# universal_front_plate_final.net
KiCad netlist of a schematic drawn in EAGLE
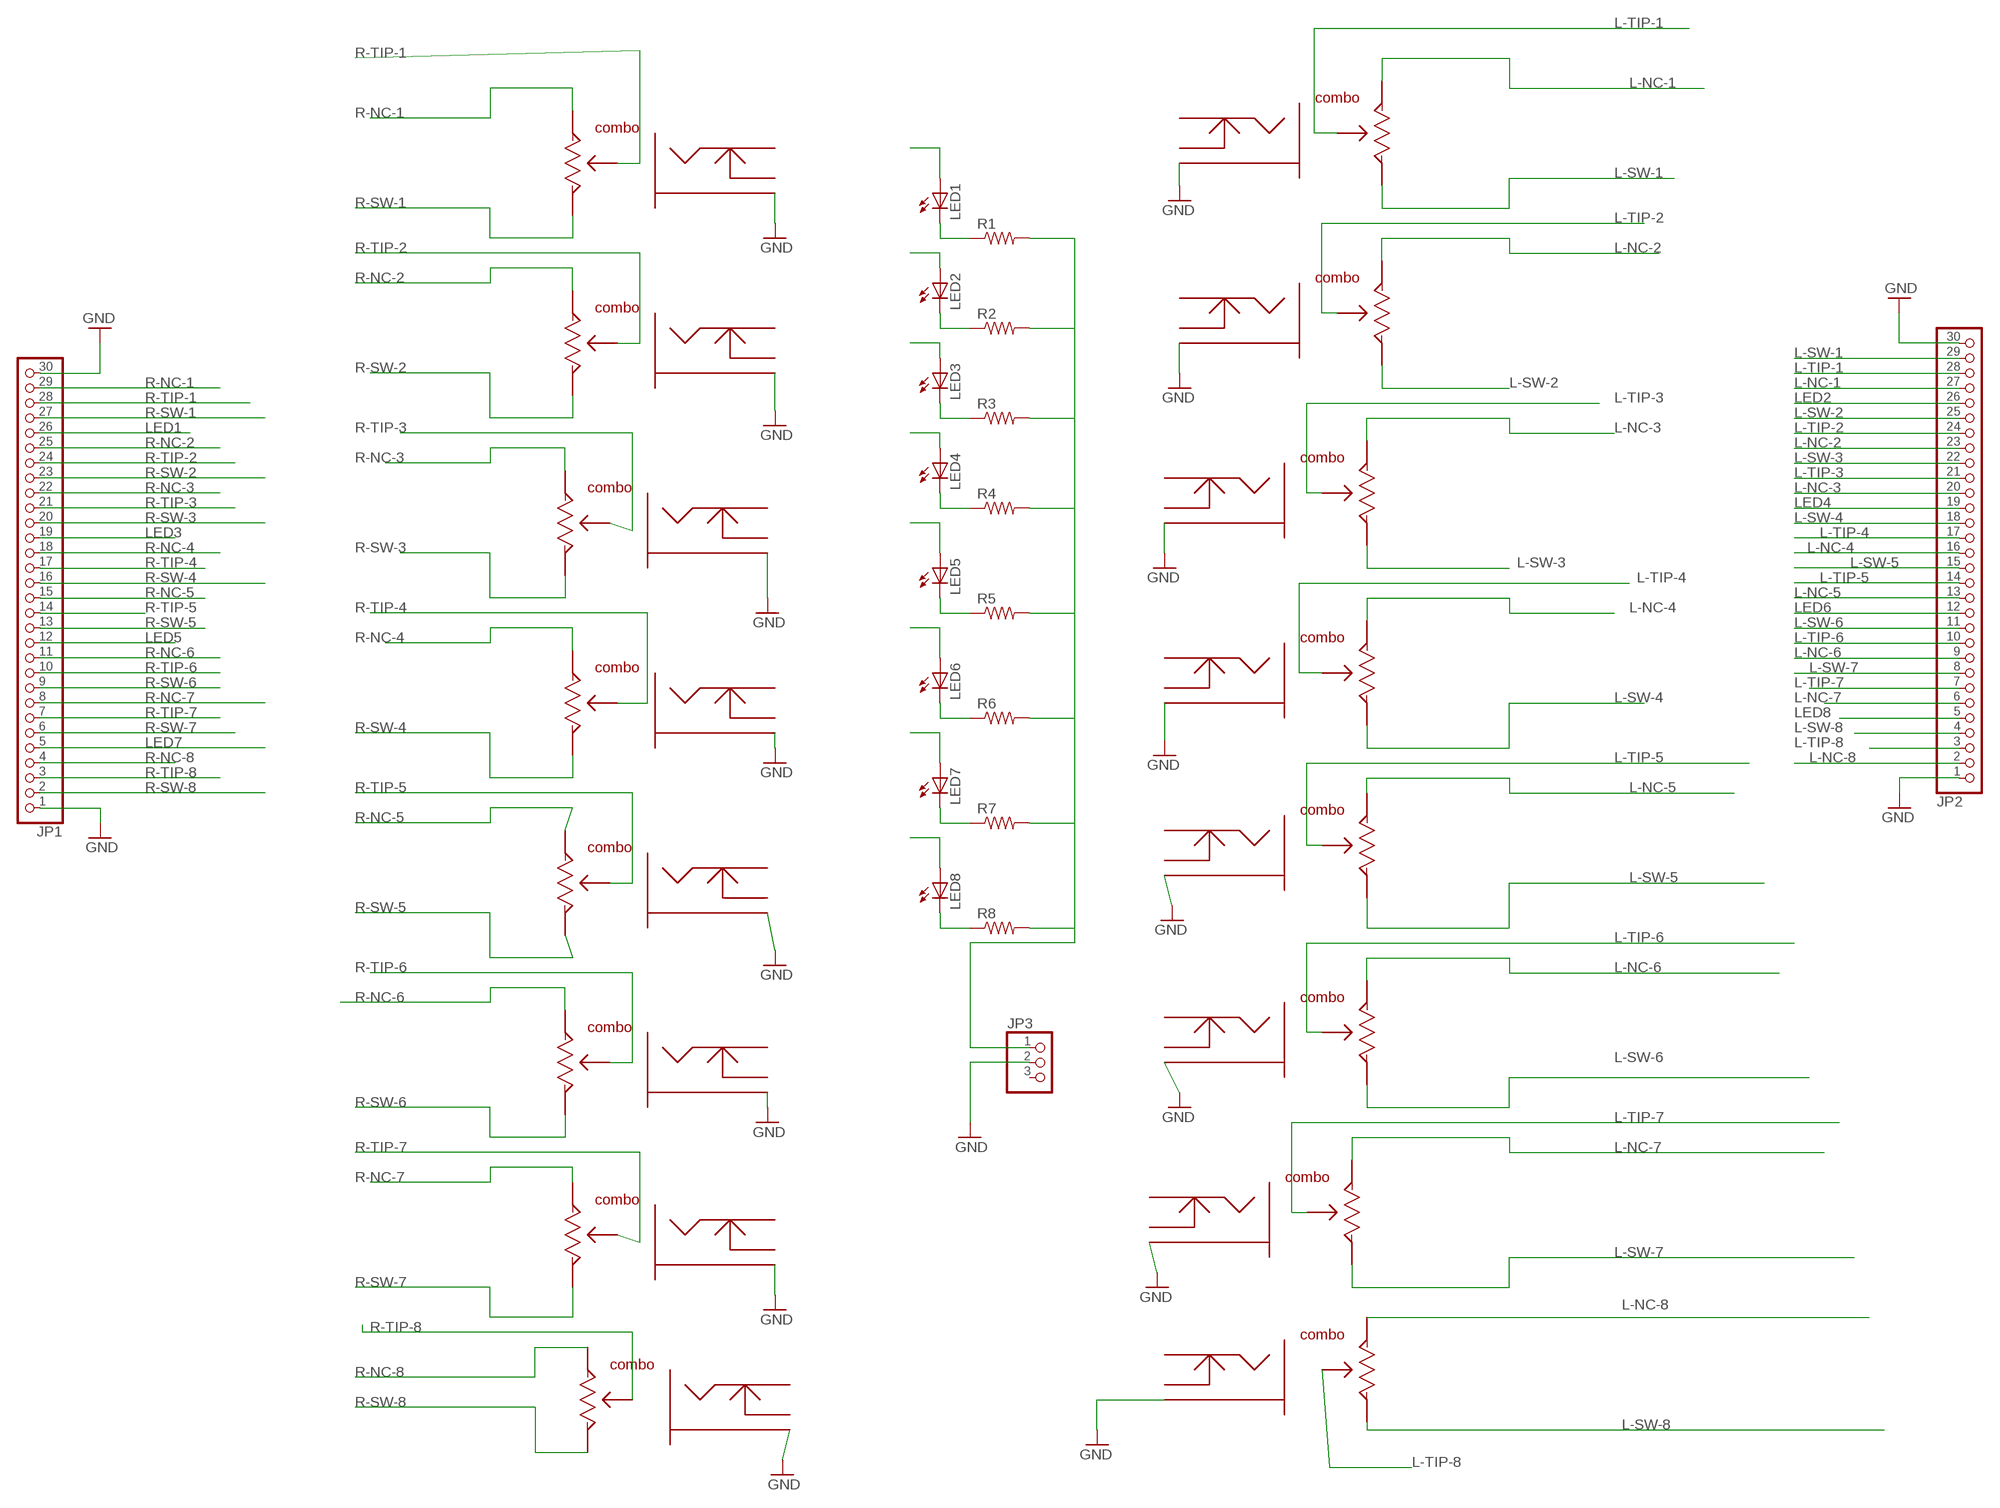
[diagram p0: schematic, sheet 1]

(export (version "E")
  (design (tool "Eeschema 10.0.6"))
  (components
    (comp (ref "JP1")
      (value "PINHD-1X30")
      (footprint "eagle-import:1X30")
      (libsource (lib "eagle-import") (part "PINHD-1X30"))
    )
    (comp (ref "JP2")
      (value "PINHD-1X30")
      (footprint "eagle-import:1X30")
      (libsource (lib "eagle-import") (part "PINHD-1X30"))
    )
    (comp (ref "JP3")
      (value "PINHD-1X3")
      (footprint "eagle-import:1X03")
      (libsource (lib "eagle-import") (part "PINHD-1X3"))
    )
    (comp (ref "LED1")
      (value "LED3MM")
      (footprint "eagle-import:LED3MM")
      (libsource (lib "eagle-import") (part "LED3MM"))
    )
    (comp (ref "LED2")
      (value "LED3MM")
      (footprint "eagle-import:LED3MM")
      (libsource (lib "eagle-import") (part "LED3MM"))
    )
    (comp (ref "LED3")
      (value "LED3MM")
      (footprint "eagle-import:LED3MM")
      (libsource (lib "eagle-import") (part "LED3MM"))
    )
    (comp (ref "LED4")
      (value "LED3MM")
      (footprint "eagle-import:LED3MM")
      (libsource (lib "eagle-import") (part "LED3MM"))
    )
    (comp (ref "LED5")
      (value "LED3MM")
      (footprint "eagle-import:LED3MM")
      (libsource (lib "eagle-import") (part "LED3MM"))
    )
    (comp (ref "LED6")
      (value "LED3MM")
      (footprint "eagle-import:LED3MM")
      (libsource (lib "eagle-import") (part "LED3MM"))
    )
    (comp (ref "LED7")
      (value "LED3MM")
      (footprint "eagle-import:LED3MM")
      (libsource (lib "eagle-import") (part "LED3MM"))
    )
    (comp (ref "LED8")
      (value "LED3MM")
      (footprint "eagle-import:LED3MM")
      (libsource (lib "eagle-import") (part "LED3MM"))
    )
    (comp (ref "R1")
      (value "R-US_0204/5")
      (footprint "eagle-import:0204_5")
      (libsource (lib "eagle-import") (part "R-US_0204/5"))
    )
    (comp (ref "R2")
      (value "R-US_0204/5")
      (footprint "eagle-import:0204_5")
      (libsource (lib "eagle-import") (part "R-US_0204/5"))
    )
    (comp (ref "R3")
      (value "R-US_0204/5")
      (footprint "eagle-import:0204_5")
      (libsource (lib "eagle-import") (part "R-US_0204/5"))
    )
    (comp (ref "R4")
      (value "R-US_0204/5")
      (footprint "eagle-import:0204_5")
      (libsource (lib "eagle-import") (part "R-US_0204/5"))
    )
    (comp (ref "R5")
      (value "R-US_0204/5")
      (footprint "eagle-import:0204_5")
      (libsource (lib "eagle-import") (part "R-US_0204/5"))
    )
    (comp (ref "R6")
      (value "R-US_0204/5")
      (footprint "eagle-import:0204_5")
      (libsource (lib "eagle-import") (part "R-US_0204/5"))
    )
    (comp (ref "R7")
      (value "R-US_0204/5")
      (footprint "eagle-import:0204_5")
      (libsource (lib "eagle-import") (part "R-US_0204/5"))
    )
    (comp (ref "R8")
      (value "R-US_0204/5")
      (footprint "eagle-import:0204_5")
      (libsource (lib "eagle-import") (part "R-US_0204/5"))
    )
    (comp (ref "U$1")
      (value "KOBICON-COMBO-NEW")
      (footprint "eagle-import:KOBICON-COMBO-NEW")
      (libsource (lib "eagle-import") (part "KOBICON-COMBO-NEW"))
    )
    (comp (ref "U$2")
      (value "KOBICON-COMBO-NEW")
      (footprint "eagle-import:KOBICON-COMBO-NEW")
      (libsource (lib "eagle-import") (part "KOBICON-COMBO-NEW"))
    )
    (comp (ref "U$3")
      (value "KOBICON-COMBO-NEW")
      (footprint "eagle-import:KOBICON-COMBO-NEW")
      (libsource (lib "eagle-import") (part "KOBICON-COMBO-NEW"))
    )
    (comp (ref "U$4")
      (value "KOBICON-COMBO-NEW")
      (footprint "eagle-import:KOBICON-COMBO-NEW")
      (libsource (lib "eagle-import") (part "KOBICON-COMBO-NEW"))
    )
    (comp (ref "U$5")
      (value "KOBICON-COMBO-NEW")
      (footprint "eagle-import:KOBICON-COMBO-NEW")
      (libsource (lib "eagle-import") (part "KOBICON-COMBO-NEW"))
    )
    (comp (ref "U$6")
      (value "KOBICON-COMBO-NEW")
      (footprint "eagle-import:KOBICON-COMBO-NEW")
      (libsource (lib "eagle-import") (part "KOBICON-COMBO-NEW"))
    )
    (comp (ref "U$7")
      (value "KOBICON-COMBO-NEW")
      (footprint "eagle-import:KOBICON-COMBO-NEW")
      (libsource (lib "eagle-import") (part "KOBICON-COMBO-NEW"))
    )
    (comp (ref "U$8")
      (value "KOBICON-COMBO-NEW")
      (footprint "eagle-import:KOBICON-COMBO-NEW")
      (libsource (lib "eagle-import") (part "KOBICON-COMBO-NEW"))
    )
    (comp (ref "U$9")
      (value "KOBICON-COMBO-NEW")
      (footprint "eagle-import:KOBICON-COMBO-NEW")
      (libsource (lib "eagle-import") (part "KOBICON-COMBO-NEW"))
    )
    (comp (ref "U$10")
      (value "KOBICON-COMBO-NEW")
      (footprint "eagle-import:KOBICON-COMBO-NEW")
      (libsource (lib "eagle-import") (part "KOBICON-COMBO-NEW"))
    )
    (comp (ref "U$11")
      (value "KOBICON-COMBO-NEW")
      (footprint "eagle-import:KOBICON-COMBO-NEW")
      (libsource (lib "eagle-import") (part "KOBICON-COMBO-NEW"))
    )
    (comp (ref "U$12")
      (value "KOBICON-COMBO-NEW")
      (footprint "eagle-import:KOBICON-COMBO-NEW")
      (libsource (lib "eagle-import") (part "KOBICON-COMBO-NEW"))
    )
    (comp (ref "U$13")
      (value "KOBICON-COMBO-NEW")
      (footprint "eagle-import:KOBICON-COMBO-NEW")
      (libsource (lib "eagle-import") (part "KOBICON-COMBO-NEW"))
    )
    (comp (ref "U$14")
      (value "KOBICON-COMBO-NEW")
      (footprint "eagle-import:KOBICON-COMBO-NEW")
      (libsource (lib "eagle-import") (part "KOBICON-COMBO-NEW"))
    )
    (comp (ref "U$15")
      (value "KOBICON-COMBO-NEW")
      (footprint "eagle-import:KOBICON-COMBO-NEW")
      (libsource (lib "eagle-import") (part "KOBICON-COMBO-NEW"))
    )
    (comp (ref "U$16")
      (value "KOBICON-COMBO-NEW")
      (footprint "eagle-import:KOBICON-COMBO-NEW")
      (libsource (lib "eagle-import") (part "KOBICON-COMBO-NEW"))
    )
  )
  (nets
    (net (code "1") (name "/L-NC-1") (class "Default")
      (node (ref "JP2") (pin "27") (pinfunction "27_27") (pintype "passive"))
      (node (ref "U$8") (pin "JACK-MID") (pinfunction "POT-L_JACK-MID") (pintype "bidirectional"))
      (node (ref "U$8") (pin "POT-L") (pinfunction "POT-L_POT-L") (pintype "bidirectional"))
    )
    (net (code "2") (name "/L-NC-2") (class "Default")
      (node (ref "JP2") (pin "23") (pinfunction "23_23") (pintype "passive"))
      (node (ref "U$9") (pin "JACK-MID") (pinfunction "POT-L_JACK-MID") (pintype "bidirectional"))
      (node (ref "U$9") (pin "POT-L") (pinfunction "POT-L_POT-L") (pintype "bidirectional"))
    )
    (net (code "3") (name "/L-NC-3") (class "Default")
      (node (ref "JP2") (pin "20") (pinfunction "20_20") (pintype "passive"))
      (node (ref "U$10") (pin "JACK-MID") (pinfunction "POT-L_JACK-MID") (pintype "bidirectional"))
      (node (ref "U$10") (pin "POT-L") (pinfunction "POT-L_POT-L") (pintype "bidirectional"))
    )
    (net (code "4") (name "/L-NC-4") (class "Default")
      (node (ref "JP2") (pin "16") (pinfunction "16_16") (pintype "passive"))
      (node (ref "U$11") (pin "JACK-MID") (pinfunction "POT-L_JACK-MID") (pintype "bidirectional"))
      (node (ref "U$11") (pin "POT-L") (pinfunction "POT-L_POT-L") (pintype "bidirectional"))
    )
    (net (code "5") (name "/L-NC-5") (class "Default")
      (node (ref "JP2") (pin "13") (pinfunction "13_13") (pintype "passive"))
      (node (ref "U$12") (pin "JACK-MID") (pinfunction "POT-L_JACK-MID") (pintype "bidirectional"))
      (node (ref "U$12") (pin "POT-L") (pinfunction "POT-L_POT-L") (pintype "bidirectional"))
    )
    (net (code "6") (name "/L-NC-6") (class "Default")
      (node (ref "JP2") (pin "9") (pinfunction "9_9") (pintype "passive"))
      (node (ref "U$13") (pin "JACK-MID") (pinfunction "POT-L_JACK-MID") (pintype "bidirectional"))
      (node (ref "U$13") (pin "POT-L") (pinfunction "POT-L_POT-L") (pintype "bidirectional"))
    )
    (net (code "7") (name "/L-NC-7") (class "Default")
      (node (ref "JP2") (pin "6") (pinfunction "6_6") (pintype "passive"))
      (node (ref "U$14") (pin "JACK-MID") (pinfunction "POT-L_JACK-MID") (pintype "bidirectional"))
      (node (ref "U$14") (pin "POT-L") (pinfunction "POT-L_POT-L") (pintype "bidirectional"))
    )
    (net (code "8") (name "/L-NC-8") (class "Default")
      (node (ref "JP2") (pin "2") (pinfunction "2_2") (pintype "passive"))
      (node (ref "U$15") (pin "JACK-MID") (pinfunction "POT-L_JACK-MID") (pintype "bidirectional"))
      (node (ref "U$15") (pin "POT-L") (pinfunction "POT-L_POT-L") (pintype "bidirectional"))
    )
    (net (code "9") (name "/L-SW-1") (class "Default")
      (node (ref "JP2") (pin "29") (pinfunction "29_29") (pintype "passive"))
      (node (ref "U$8") (pin "JACK-BOT") (pinfunction "POT-R_JACK-BOT") (pintype "bidirectional"))
      (node (ref "U$8") (pin "POT-R") (pinfunction "POT-R_POT-R") (pintype "bidirectional"))
    )
    (net (code "10") (name "/L-SW-2") (class "Default")
      (node (ref "JP2") (pin "25") (pinfunction "25_25") (pintype "passive"))
      (node (ref "U$9") (pin "JACK-BOT") (pinfunction "POT-R_JACK-BOT") (pintype "bidirectional"))
      (node (ref "U$9") (pin "POT-R") (pinfunction "POT-R_POT-R") (pintype "bidirectional"))
    )
    (net (code "11") (name "/L-SW-3") (class "Default")
      (node (ref "JP2") (pin "22") (pinfunction "22_22") (pintype "passive"))
      (node (ref "U$10") (pin "JACK-BOT") (pinfunction "POT-R_JACK-BOT") (pintype "bidirectional"))
      (node (ref "U$10") (pin "POT-R") (pinfunction "POT-R_POT-R") (pintype "bidirectional"))
    )
    (net (code "12") (name "/L-SW-4") (class "Default")
      (node (ref "JP2") (pin "18") (pinfunction "18_18") (pintype "passive"))
      (node (ref "U$11") (pin "JACK-BOT") (pinfunction "POT-R_JACK-BOT") (pintype "bidirectional"))
      (node (ref "U$11") (pin "POT-R") (pinfunction "POT-R_POT-R") (pintype "bidirectional"))
    )
    (net (code "13") (name "/L-SW-5") (class "Default")
      (node (ref "JP2") (pin "15") (pinfunction "15_15") (pintype "passive"))
      (node (ref "U$12") (pin "JACK-BOT") (pinfunction "POT-R_JACK-BOT") (pintype "bidirectional"))
      (node (ref "U$12") (pin "POT-R") (pinfunction "POT-R_POT-R") (pintype "bidirectional"))
    )
    (net (code "14") (name "/L-SW-6") (class "Default")
      (node (ref "JP2") (pin "11") (pinfunction "11_11") (pintype "passive"))
      (node (ref "U$13") (pin "JACK-BOT") (pinfunction "POT-R_JACK-BOT") (pintype "bidirectional"))
      (node (ref "U$13") (pin "POT-R") (pinfunction "POT-R_POT-R") (pintype "bidirectional"))
    )
    (net (code "15") (name "/L-SW-7") (class "Default")
      (node (ref "JP2") (pin "8") (pinfunction "8_8") (pintype "passive"))
      (node (ref "U$14") (pin "JACK-BOT") (pinfunction "POT-R_JACK-BOT") (pintype "bidirectional"))
      (node (ref "U$14") (pin "POT-R") (pinfunction "POT-R_POT-R") (pintype "bidirectional"))
    )
    (net (code "16") (name "/L-SW-8") (class "Default")
      (node (ref "JP2") (pin "4") (pinfunction "4_4") (pintype "passive"))
      (node (ref "U$15") (pin "JACK-BOT") (pinfunction "POT-R_JACK-BOT") (pintype "bidirectional"))
      (node (ref "U$15") (pin "POT-R") (pinfunction "POT-R_POT-R") (pintype "bidirectional"))
    )
    (net (code "17") (name "/L-TIP-1") (class "Default")
      (node (ref "JP2") (pin "28") (pinfunction "28_28") (pintype "passive"))
      (node (ref "U$8") (pin "JACK-TOP") (pinfunction "POT-MID_JACK-TOP") (pintype "bidirectional"))
      (node (ref "U$8") (pin "POT-MID") (pinfunction "POT-MID_POT-MID") (pintype "bidirectional"))
    )
    (net (code "18") (name "/L-TIP-2") (class "Default")
      (node (ref "JP2") (pin "24") (pinfunction "24_24") (pintype "passive"))
      (node (ref "U$9") (pin "JACK-TOP") (pinfunction "POT-MID_JACK-TOP") (pintype "bidirectional"))
      (node (ref "U$9") (pin "POT-MID") (pinfunction "POT-MID_POT-MID") (pintype "bidirectional"))
    )
    (net (code "19") (name "/L-TIP-3") (class "Default")
      (node (ref "JP2") (pin "21") (pinfunction "21_21") (pintype "passive"))
      (node (ref "U$10") (pin "JACK-TOP") (pinfunction "POT-MID_JACK-TOP") (pintype "bidirectional"))
      (node (ref "U$10") (pin "POT-MID") (pinfunction "POT-MID_POT-MID") (pintype "bidirectional"))
    )
    (net (code "20") (name "/L-TIP-4") (class "Default")
      (node (ref "JP2") (pin "17") (pinfunction "17_17") (pintype "passive"))
      (node (ref "U$11") (pin "JACK-TOP") (pinfunction "POT-MID_JACK-TOP") (pintype "bidirectional"))
      (node (ref "U$11") (pin "POT-MID") (pinfunction "POT-MID_POT-MID") (pintype "bidirectional"))
    )
    (net (code "21") (name "/L-TIP-5") (class "Default")
      (node (ref "JP2") (pin "14") (pinfunction "14_14") (pintype "passive"))
      (node (ref "U$12") (pin "JACK-TOP") (pinfunction "POT-MID_JACK-TOP") (pintype "bidirectional"))
      (node (ref "U$12") (pin "POT-MID") (pinfunction "POT-MID_POT-MID") (pintype "bidirectional"))
    )
    (net (code "22") (name "/L-TIP-6") (class "Default")
      (node (ref "JP2") (pin "10") (pinfunction "10_10") (pintype "passive"))
      (node (ref "U$13") (pin "JACK-TOP") (pinfunction "POT-MID_JACK-TOP") (pintype "bidirectional"))
      (node (ref "U$13") (pin "POT-MID") (pinfunction "POT-MID_POT-MID") (pintype "bidirectional"))
    )
    (net (code "23") (name "/L-TIP-7") (class "Default")
      (node (ref "JP2") (pin "7") (pinfunction "7_7") (pintype "passive"))
      (node (ref "U$14") (pin "JACK-TOP") (pinfunction "POT-MID_JACK-TOP") (pintype "bidirectional"))
      (node (ref "U$14") (pin "POT-MID") (pinfunction "POT-MID_POT-MID") (pintype "bidirectional"))
    )
    (net (code "24") (name "/L-TIP-8") (class "Default")
      (node (ref "JP2") (pin "3") (pinfunction "3_3") (pintype "passive"))
      (node (ref "U$15") (pin "JACK-TOP") (pinfunction "POT-MID_JACK-TOP") (pintype "bidirectional"))
      (node (ref "U$15") (pin "POT-MID") (pinfunction "POT-MID_POT-MID") (pintype "bidirectional"))
    )
    (net (code "25") (name "/LED1") (class "Default")
      (node (ref "JP1") (pin "26") (pinfunction "26_26") (pintype "passive"))
      (node (ref "LED1") (pin "A") (pinfunction "A_A") (pintype "passive"))
    )
    (net (code "26") (name "/LED2") (class "Default")
      (node (ref "JP2") (pin "26") (pinfunction "26_26") (pintype "passive"))
      (node (ref "LED2") (pin "A") (pinfunction "A_A") (pintype "passive"))
    )
    (net (code "27") (name "/LED3") (class "Default")
      (node (ref "JP1") (pin "19") (pinfunction "19_19") (pintype "passive"))
      (node (ref "LED3") (pin "A") (pinfunction "A_A") (pintype "passive"))
    )
    (net (code "28") (name "/LED4") (class "Default")
      (node (ref "JP2") (pin "19") (pinfunction "19_19") (pintype "passive"))
      (node (ref "LED4") (pin "A") (pinfunction "A_A") (pintype "passive"))
    )
    (net (code "29") (name "/LED5") (class "Default")
      (node (ref "JP1") (pin "12") (pinfunction "12_12") (pintype "passive"))
      (node (ref "LED5") (pin "A") (pinfunction "A_A") (pintype "passive"))
    )
    (net (code "30") (name "/LED6") (class "Default")
      (node (ref "JP2") (pin "12") (pinfunction "12_12") (pintype "passive"))
      (node (ref "LED6") (pin "A") (pinfunction "A_A") (pintype "passive"))
    )
    (net (code "31") (name "/LED7") (class "Default")
      (node (ref "JP1") (pin "5") (pinfunction "5_5") (pintype "passive"))
      (node (ref "LED7") (pin "A") (pinfunction "A_A") (pintype "passive"))
    )
    (net (code "32") (name "/LED8") (class "Default")
      (node (ref "JP2") (pin "5") (pinfunction "5_5") (pintype "passive"))
      (node (ref "LED8") (pin "A") (pinfunction "A_A") (pintype "passive"))
    )
    (net (code "33") (name "/R-NC-1") (class "Default")
      (node (ref "JP1") (pin "29") (pinfunction "29_29") (pintype "passive"))
      (node (ref "U$1") (pin "JACK-MID") (pinfunction "POT-L_JACK-MID") (pintype "bidirectional"))
      (node (ref "U$1") (pin "POT-L") (pinfunction "POT-L_POT-L") (pintype "bidirectional"))
    )
    (net (code "34") (name "/R-NC-2") (class "Default")
      (node (ref "JP1") (pin "25") (pinfunction "25_25") (pintype "passive"))
      (node (ref "U$2") (pin "JACK-MID") (pinfunction "POT-L_JACK-MID") (pintype "bidirectional"))
      (node (ref "U$2") (pin "POT-L") (pinfunction "POT-L_POT-L") (pintype "bidirectional"))
    )
    (net (code "35") (name "/R-NC-3") (class "Default")
      (node (ref "JP1") (pin "22") (pinfunction "22_22") (pintype "passive"))
      (node (ref "U$3") (pin "JACK-MID") (pinfunction "POT-L_JACK-MID") (pintype "bidirectional"))
      (node (ref "U$3") (pin "POT-L") (pinfunction "POT-L_POT-L") (pintype "bidirectional"))
    )
    (net (code "36") (name "/R-NC-4") (class "Default")
      (node (ref "JP1") (pin "18") (pinfunction "18_18") (pintype "passive"))
      (node (ref "U$4") (pin "JACK-MID") (pinfunction "POT-L_JACK-MID") (pintype "bidirectional"))
      (node (ref "U$4") (pin "POT-L") (pinfunction "POT-L_POT-L") (pintype "bidirectional"))
    )
    (net (code "37") (name "/R-NC-5") (class "Default")
      (node (ref "JP1") (pin "15") (pinfunction "15_15") (pintype "passive"))
      (node (ref "U$5") (pin "JACK-MID") (pinfunction "POT-L_JACK-MID") (pintype "bidirectional"))
      (node (ref "U$5") (pin "POT-L") (pinfunction "POT-L_POT-L") (pintype "bidirectional"))
    )
    (net (code "38") (name "/R-NC-6") (class "Default")
      (node (ref "JP1") (pin "11") (pinfunction "11_11") (pintype "passive"))
      (node (ref "U$6") (pin "JACK-MID") (pinfunction "POT-L_JACK-MID") (pintype "bidirectional"))
      (node (ref "U$6") (pin "POT-L") (pinfunction "POT-L_POT-L") (pintype "bidirectional"))
    )
    (net (code "39") (name "/R-NC-7") (class "Default")
      (node (ref "JP1") (pin "8") (pinfunction "8_8") (pintype "passive"))
      (node (ref "U$7") (pin "JACK-MID") (pinfunction "POT-L_JACK-MID") (pintype "bidirectional"))
      (node (ref "U$7") (pin "POT-L") (pinfunction "POT-L_POT-L") (pintype "bidirectional"))
    )
    (net (code "40") (name "/R-NC-8") (class "Default")
      (node (ref "JP1") (pin "4") (pinfunction "4_4") (pintype "passive"))
      (node (ref "U$16") (pin "JACK-MID") (pinfunction "POT-L_JACK-MID") (pintype "bidirectional"))
      (node (ref "U$16") (pin "POT-L") (pinfunction "POT-L_POT-L") (pintype "bidirectional"))
    )
    (net (code "41") (name "/R-SW-1") (class "Default")
      (node (ref "JP1") (pin "27") (pinfunction "27_27") (pintype "passive"))
      (node (ref "U$1") (pin "JACK-BOT") (pinfunction "POT-R_JACK-BOT") (pintype "bidirectional"))
      (node (ref "U$1") (pin "POT-R") (pinfunction "POT-R_POT-R") (pintype "bidirectional"))
    )
    (net (code "42") (name "/R-SW-2") (class "Default")
      (node (ref "JP1") (pin "23") (pinfunction "23_23") (pintype "passive"))
      (node (ref "U$2") (pin "JACK-BOT") (pinfunction "POT-R_JACK-BOT") (pintype "bidirectional"))
      (node (ref "U$2") (pin "POT-R") (pinfunction "POT-R_POT-R") (pintype "bidirectional"))
    )
    (net (code "43") (name "/R-SW-3") (class "Default")
      (node (ref "JP1") (pin "20") (pinfunction "20_20") (pintype "passive"))
      (node (ref "U$3") (pin "JACK-BOT") (pinfunction "POT-R_JACK-BOT") (pintype "bidirectional"))
      (node (ref "U$3") (pin "POT-R") (pinfunction "POT-R_POT-R") (pintype "bidirectional"))
    )
    (net (code "44") (name "/R-SW-4") (class "Default")
      (node (ref "JP1") (pin "16") (pinfunction "16_16") (pintype "passive"))
      (node (ref "U$4") (pin "JACK-BOT") (pinfunction "POT-R_JACK-BOT") (pintype "bidirectional"))
      (node (ref "U$4") (pin "POT-R") (pinfunction "POT-R_POT-R") (pintype "bidirectional"))
    )
    (net (code "45") (name "/R-SW-5") (class "Default")
      (node (ref "JP1") (pin "13") (pinfunction "13_13") (pintype "passive"))
      (node (ref "U$5") (pin "JACK-BOT") (pinfunction "POT-R_JACK-BOT") (pintype "bidirectional"))
      (node (ref "U$5") (pin "POT-R") (pinfunction "POT-R_POT-R") (pintype "bidirectional"))
    )
    (net (code "46") (name "/R-SW-6") (class "Default")
      (node (ref "JP1") (pin "9") (pinfunction "9_9") (pintype "passive"))
      (node (ref "U$6") (pin "JACK-BOT") (pinfunction "POT-R_JACK-BOT") (pintype "bidirectional"))
      (node (ref "U$6") (pin "POT-R") (pinfunction "POT-R_POT-R") (pintype "bidirectional"))
    )
    (net (code "47") (name "/R-SW-7") (class "Default")
      (node (ref "JP1") (pin "6") (pinfunction "6_6") (pintype "passive"))
      (node (ref "U$7") (pin "JACK-BOT") (pinfunction "POT-R_JACK-BOT") (pintype "bidirectional"))
      (node (ref "U$7") (pin "POT-R") (pinfunction "POT-R_POT-R") (pintype "bidirectional"))
    )
    (net (code "48") (name "/R-SW-8") (class "Default")
      (node (ref "JP1") (pin "2") (pinfunction "2_2") (pintype "passive"))
      (node (ref "U$16") (pin "JACK-BOT") (pinfunction "POT-R_JACK-BOT") (pintype "bidirectional"))
      (node (ref "U$16") (pin "POT-R") (pinfunction "POT-R_POT-R") (pintype "bidirectional"))
    )
    (net (code "49") (name "/R-TIP-1") (class "Default")
      (node (ref "JP1") (pin "28") (pinfunction "28_28") (pintype "passive"))
      (node (ref "U$1") (pin "JACK-TOP") (pinfunction "POT-MID_JACK-TOP") (pintype "bidirectional"))
      (node (ref "U$1") (pin "POT-MID") (pinfunction "POT-MID_POT-MID") (pintype "bidirectional"))
    )
    (net (code "50") (name "/R-TIP-2") (class "Default")
      (node (ref "JP1") (pin "24") (pinfunction "24_24") (pintype "passive"))
      (node (ref "U$2") (pin "JACK-TOP") (pinfunction "POT-MID_JACK-TOP") (pintype "bidirectional"))
      (node (ref "U$2") (pin "POT-MID") (pinfunction "POT-MID_POT-MID") (pintype "bidirectional"))
    )
    (net (code "51") (name "/R-TIP-3") (class "Default")
      (node (ref "JP1") (pin "21") (pinfunction "21_21") (pintype "passive"))
      (node (ref "U$3") (pin "JACK-TOP") (pinfunction "POT-MID_JACK-TOP") (pintype "bidirectional"))
      (node (ref "U$3") (pin "POT-MID") (pinfunction "POT-MID_POT-MID") (pintype "bidirectional"))
    )
    (net (code "52") (name "/R-TIP-4") (class "Default")
      (node (ref "JP1") (pin "17") (pinfunction "17_17") (pintype "passive"))
      (node (ref "U$4") (pin "JACK-TOP") (pinfunction "POT-MID_JACK-TOP") (pintype "bidirectional"))
      (node (ref "U$4") (pin "POT-MID") (pinfunction "POT-MID_POT-MID") (pintype "bidirectional"))
    )
    (net (code "53") (name "/R-TIP-5") (class "Default")
      (node (ref "JP1") (pin "14") (pinfunction "14_14") (pintype "passive"))
      (node (ref "U$5") (pin "JACK-TOP") (pinfunction "POT-MID_JACK-TOP") (pintype "bidirectional"))
      (node (ref "U$5") (pin "POT-MID") (pinfunction "POT-MID_POT-MID") (pintype "bidirectional"))
    )
    (net (code "54") (name "/R-TIP-6") (class "Default")
      (node (ref "JP1") (pin "10") (pinfunction "10_10") (pintype "passive"))
      (node (ref "U$6") (pin "JACK-TOP") (pinfunction "POT-MID_JACK-TOP") (pintype "bidirectional"))
      (node (ref "U$6") (pin "POT-MID") (pinfunction "POT-MID_POT-MID") (pintype "bidirectional"))
    )
    (net (code "55") (name "/R-TIP-7") (class "Default")
      (node (ref "JP1") (pin "7") (pinfunction "7_7") (pintype "passive"))
      (node (ref "U$7") (pin "JACK-TOP") (pinfunction "POT-MID_JACK-TOP") (pintype "bidirectional"))
      (node (ref "U$7") (pin "POT-MID") (pinfunction "POT-MID_POT-MID") (pintype "bidirectional"))
    )
    (net (code "56") (name "/R-TIP-8") (class "Default")
      (node (ref "JP1") (pin "3") (pinfunction "3_3") (pintype "passive"))
      (node (ref "U$16") (pin "JACK-TOP") (pinfunction "POT-MID_JACK-TOP") (pintype "bidirectional"))
      (node (ref "U$16") (pin "POT-MID") (pinfunction "POT-MID_POT-MID") (pintype "bidirectional"))
    )
    (net (code "57") (name "GND") (class "Default")
      (node (ref "JP1") (pin "1") (pinfunction "1_1") (pintype "passive"))
      (node (ref "JP1") (pin "30") (pinfunction "30_30") (pintype "passive"))
      (node (ref "JP2") (pin "1") (pinfunction "1_1") (pintype "passive"))
      (node (ref "JP2") (pin "30") (pinfunction "30_30") (pintype "passive"))
      (node (ref "JP3") (pin "2") (pinfunction "2_2") (pintype "passive"))
      (node (ref "U$1") (pin "GND") (pinfunction "JACK-GND_GND") (pintype "bidirectional"))
      (node (ref "U$1") (pin "GND2") (pinfunction "JACK-GND_GND2") (pintype "bidirectional"))
      (node (ref "U$10") (pin "GND") (pinfunction "JACK-GND_GND") (pintype "bidirectional"))
      (node (ref "U$10") (pin "GND2") (pinfunction "JACK-GND_GND2") (pintype "bidirectional"))
      (node (ref "U$11") (pin "GND") (pinfunction "JACK-GND_GND") (pintype "bidirectional"))
      (node (ref "U$11") (pin "GND2") (pinfunction "JACK-GND_GND2") (pintype "bidirectional"))
      (node (ref "U$12") (pin "GND") (pinfunction "JACK-GND_GND") (pintype "bidirectional"))
      (node (ref "U$12") (pin "GND2") (pinfunction "JACK-GND_GND2") (pintype "bidirectional"))
      (node (ref "U$13") (pin "GND") (pinfunction "JACK-GND_GND") (pintype "bidirectional"))
      (node (ref "U$13") (pin "GND2") (pinfunction "JACK-GND_GND2") (pintype "bidirectional"))
      (node (ref "U$14") (pin "GND") (pinfunction "JACK-GND_GND") (pintype "bidirectional"))
      (node (ref "U$14") (pin "GND2") (pinfunction "JACK-GND_GND2") (pintype "bidirectional"))
      (node (ref "U$15") (pin "GND") (pinfunction "JACK-GND_GND") (pintype "bidirectional"))
      (node (ref "U$15") (pin "GND2") (pinfunction "JACK-GND_GND2") (pintype "bidirectional"))
      (node (ref "U$16") (pin "GND") (pinfunction "JACK-GND_GND") (pintype "bidirectional"))
      (node (ref "U$16") (pin "GND2") (pinfunction "JACK-GND_GND2") (pintype "bidirectional"))
      (node (ref "U$2") (pin "GND") (pinfunction "JACK-GND_GND") (pintype "bidirectional"))
      (node (ref "U$2") (pin "GND2") (pinfunction "JACK-GND_GND2") (pintype "bidirectional"))
      (node (ref "U$3") (pin "GND") (pinfunction "JACK-GND_GND") (pintype "bidirectional"))
      (node (ref "U$3") (pin "GND2") (pinfunction "JACK-GND_GND2") (pintype "bidirectional"))
      (node (ref "U$4") (pin "GND") (pinfunction "JACK-GND_GND") (pintype "bidirectional"))
      (node (ref "U$4") (pin "GND2") (pinfunction "JACK-GND_GND2") (pintype "bidirectional"))
      (node (ref "U$5") (pin "GND") (pinfunction "JACK-GND_GND") (pintype "bidirectional"))
      (node (ref "U$5") (pin "GND2") (pinfunction "JACK-GND_GND2") (pintype "bidirectional"))
      (node (ref "U$6") (pin "GND") (pinfunction "JACK-GND_GND") (pintype "bidirectional"))
      (node (ref "U$6") (pin "GND2") (pinfunction "JACK-GND_GND2") (pintype "bidirectional"))
      (node (ref "U$7") (pin "GND") (pinfunction "JACK-GND_GND") (pintype "bidirectional"))
      (node (ref "U$7") (pin "GND2") (pinfunction "JACK-GND_GND2") (pintype "bidirectional"))
      (node (ref "U$8") (pin "GND") (pinfunction "JACK-GND_GND") (pintype "bidirectional"))
      (node (ref "U$8") (pin "GND2") (pinfunction "JACK-GND_GND2") (pintype "bidirectional"))
      (node (ref "U$9") (pin "GND") (pinfunction "JACK-GND_GND") (pintype "bidirectional"))
      (node (ref "U$9") (pin "GND2") (pinfunction "JACK-GND_GND2") (pintype "bidirectional"))
    )
    (net (code "58") (name "Net-(JP3-Pad1)") (class "Default")
      (node (ref "JP3") (pin "1") (pinfunction "1_1") (pintype "passive"))
      (node (ref "R1") (pin "2") (pinfunction "2_2") (pintype "passive"))
      (node (ref "R2") (pin "2") (pinfunction "2_2") (pintype "passive"))
      (node (ref "R3") (pin "2") (pinfunction "2_2") (pintype "passive"))
      (node (ref "R4") (pin "2") (pinfunction "2_2") (pintype "passive"))
      (node (ref "R5") (pin "2") (pinfunction "2_2") (pintype "passive"))
      (node (ref "R6") (pin "2") (pinfunction "2_2") (pintype "passive"))
      (node (ref "R7") (pin "2") (pinfunction "2_2") (pintype "passive"))
      (node (ref "R8") (pin "2") (pinfunction "2_2") (pintype "passive"))
    )
    (net (code "59") (name "Net-(LED1-C)") (class "Default")
      (node (ref "LED1") (pin "K") (pinfunction "C_K") (pintype "passive"))
      (node (ref "R1") (pin "1") (pinfunction "1_1") (pintype "passive"))
    )
    (net (code "60") (name "Net-(LED2-C)") (class "Default")
      (node (ref "LED2") (pin "K") (pinfunction "C_K") (pintype "passive"))
      (node (ref "R2") (pin "1") (pinfunction "1_1") (pintype "passive"))
    )
    (net (code "61") (name "Net-(LED3-C)") (class "Default")
      (node (ref "LED3") (pin "K") (pinfunction "C_K") (pintype "passive"))
      (node (ref "R3") (pin "1") (pinfunction "1_1") (pintype "passive"))
    )
    (net (code "62") (name "Net-(LED4-C)") (class "Default")
      (node (ref "LED4") (pin "K") (pinfunction "C_K") (pintype "passive"))
      (node (ref "R4") (pin "1") (pinfunction "1_1") (pintype "passive"))
    )
    (net (code "63") (name "Net-(LED5-C)") (class "Default")
      (node (ref "LED5") (pin "K") (pinfunction "C_K") (pintype "passive"))
      (node (ref "R5") (pin "1") (pinfunction "1_1") (pintype "passive"))
    )
    (net (code "64") (name "Net-(LED6-C)") (class "Default")
      (node (ref "LED6") (pin "K") (pinfunction "C_K") (pintype "passive"))
      (node (ref "R6") (pin "1") (pinfunction "1_1") (pintype "passive"))
    )
    (net (code "65") (name "Net-(LED7-C)") (class "Default")
      (node (ref "LED7") (pin "K") (pinfunction "C_K") (pintype "passive"))
      (node (ref "R7") (pin "1") (pinfunction "1_1") (pintype "passive"))
    )
    (net (code "66") (name "Net-(LED8-C)") (class "Default")
      (node (ref "LED8") (pin "K") (pinfunction "C_K") (pintype "passive"))
      (node (ref "R8") (pin "1") (pinfunction "1_1") (pintype "passive"))
    )
    (net (code "67") (name "unconnected-(JP3-Pad3)") (class "Default")
      (node (ref "JP3") (pin "3") (pinfunction "3_3") (pintype "passive"))
    )
  )
)
